# F3N-ADXL377-BREAKOUT.net
KiCad netlist of a schematic drawn in EAGLE
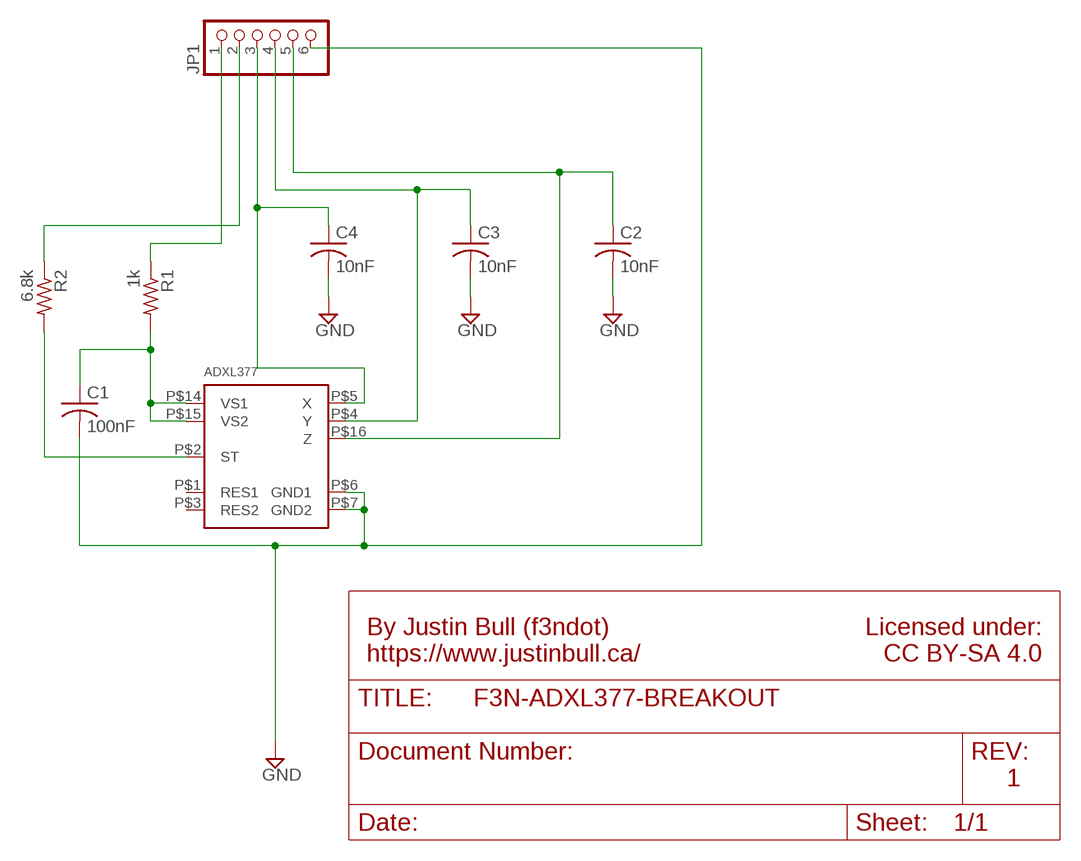
[diagram p0: schematic, sheet 1]

(export (version "E")
  (design (tool "Eeschema 10.0.6"))
  (components
    (comp (ref "ADXL377")
      (value "ACCEL_ADXL377LFCSP_LQ")
      (footprint "eagle-import:LFCSP_LQ_CP-16-28")
      (libsource (lib "eagle-import") (part "ACCEL_ADXL377LFCSP_LQ"))
    )
    (comp (ref "C1")
      (value "100nF")
      (footprint "eagle-import:C050-030X075")
      (libsource (lib "eagle-import") (part "C-US050-030X075"))
    )
    (comp (ref "C2")
      (value "10nF")
      (footprint "eagle-import:C050-030X075")
      (libsource (lib "eagle-import") (part "C-US050-030X075"))
    )
    (comp (ref "C3")
      (value "10nF")
      (footprint "eagle-import:C050-030X075")
      (libsource (lib "eagle-import") (part "C-US050-030X075"))
    )
    (comp (ref "C4")
      (value "10nF")
      (footprint "eagle-import:C050-030X075")
      (libsource (lib "eagle-import") (part "C-US050-030X075"))
    )
    (comp (ref "JP1")
      (value "PINHD-1X6")
      (footprint "eagle-import:1X06")
      (libsource (lib "eagle-import") (part "PINHD-1X6"))
    )
    (comp (ref "R1")
      (value "1k")
      (footprint "eagle-import:0204_7")
      (libsource (lib "eagle-import") (part "R-US_0204/7"))
    )
    (comp (ref "R2")
      (value "6.8k")
      (footprint "eagle-import:0204_7")
      (libsource (lib "eagle-import") (part "R-US_0204/7"))
    )
  )
  (nets
    (net (code "1") (name "GND") (class "Default")
      (node (ref "ADXL377") (pin "P$6") (pinfunction "GND1_P$6") (pintype "bidirectional"))
      (node (ref "ADXL377") (pin "P$7") (pinfunction "GND2_P$7") (pintype "bidirectional"))
      (node (ref "C1") (pin "2") (pinfunction "2_2") (pintype "passive"))
      (node (ref "C2") (pin "2") (pinfunction "2_2") (pintype "passive"))
      (node (ref "C3") (pin "2") (pinfunction "2_2") (pintype "passive"))
      (node (ref "C4") (pin "2") (pinfunction "2_2") (pintype "passive"))
      (node (ref "JP1") (pin "6") (pinfunction "6_6") (pintype "passive"))
    )
    (net (code "2") (name "Net-(ADXL377-ST)") (class "Default")
      (node (ref "ADXL377") (pin "P$2") (pinfunction "ST_P$2") (pintype "bidirectional"))
      (node (ref "R2") (pin "2") (pinfunction "2_2") (pintype "passive"))
    )
    (net (code "3") (name "Net-(ADXL377-VS1)") (class "Default")
      (node (ref "ADXL377") (pin "P$14") (pinfunction "VS1_P$14") (pintype "power_in"))
      (node (ref "ADXL377") (pin "P$15") (pinfunction "VS2_P$15") (pintype "power_in"))
      (node (ref "C1") (pin "1") (pinfunction "1_1") (pintype "passive"))
      (node (ref "R1") (pin "2") (pinfunction "2_2") (pintype "passive"))
    )
    (net (code "4") (name "Net-(ADXL377-X)") (class "Default")
      (node (ref "ADXL377") (pin "P$5") (pinfunction "X_P$5") (pintype "output"))
      (node (ref "C4") (pin "1") (pinfunction "1_1") (pintype "passive"))
      (node (ref "JP1") (pin "3") (pinfunction "3_3") (pintype "passive"))
    )
    (net (code "5") (name "Net-(ADXL377-Y)") (class "Default")
      (node (ref "ADXL377") (pin "P$4") (pinfunction "Y_P$4") (pintype "output"))
      (node (ref "C3") (pin "1") (pinfunction "1_1") (pintype "passive"))
      (node (ref "JP1") (pin "4") (pinfunction "4_4") (pintype "passive"))
    )
    (net (code "6") (name "Net-(ADXL377-Z)") (class "Default")
      (node (ref "ADXL377") (pin "P$16") (pinfunction "Z_P$16") (pintype "output"))
      (node (ref "C2") (pin "1") (pinfunction "1_1") (pintype "passive"))
      (node (ref "JP1") (pin "5") (pinfunction "5_5") (pintype "passive"))
    )
    (net (code "7") (name "Net-(JP1-Pad1)") (class "Default")
      (node (ref "JP1") (pin "1") (pinfunction "1_1") (pintype "passive"))
      (node (ref "R1") (pin "1") (pinfunction "1_1") (pintype "passive"))
    )
    (net (code "8") (name "Net-(JP1-Pad2)") (class "Default")
      (node (ref "JP1") (pin "2") (pinfunction "2_2") (pintype "passive"))
      (node (ref "R2") (pin "1") (pinfunction "1_1") (pintype "passive"))
    )
    (net (code "9") (name "unconnected-(ADXL377-RES1-PadP$1)") (class "Default")
      (node (ref "ADXL377") (pin "P$1") (pinfunction "RES1_P$1") (pintype "bidirectional"))
    )
    (net (code "10") (name "unconnected-(ADXL377-RES2-PadP$3)") (class "Default")
      (node (ref "ADXL377") (pin "P$3") (pinfunction "RES2_P$3") (pintype "bidirectional"))
    )
  )
)
